# can-stm32g4.net
KiCad netlist of a schematic drawn in Altium Designer
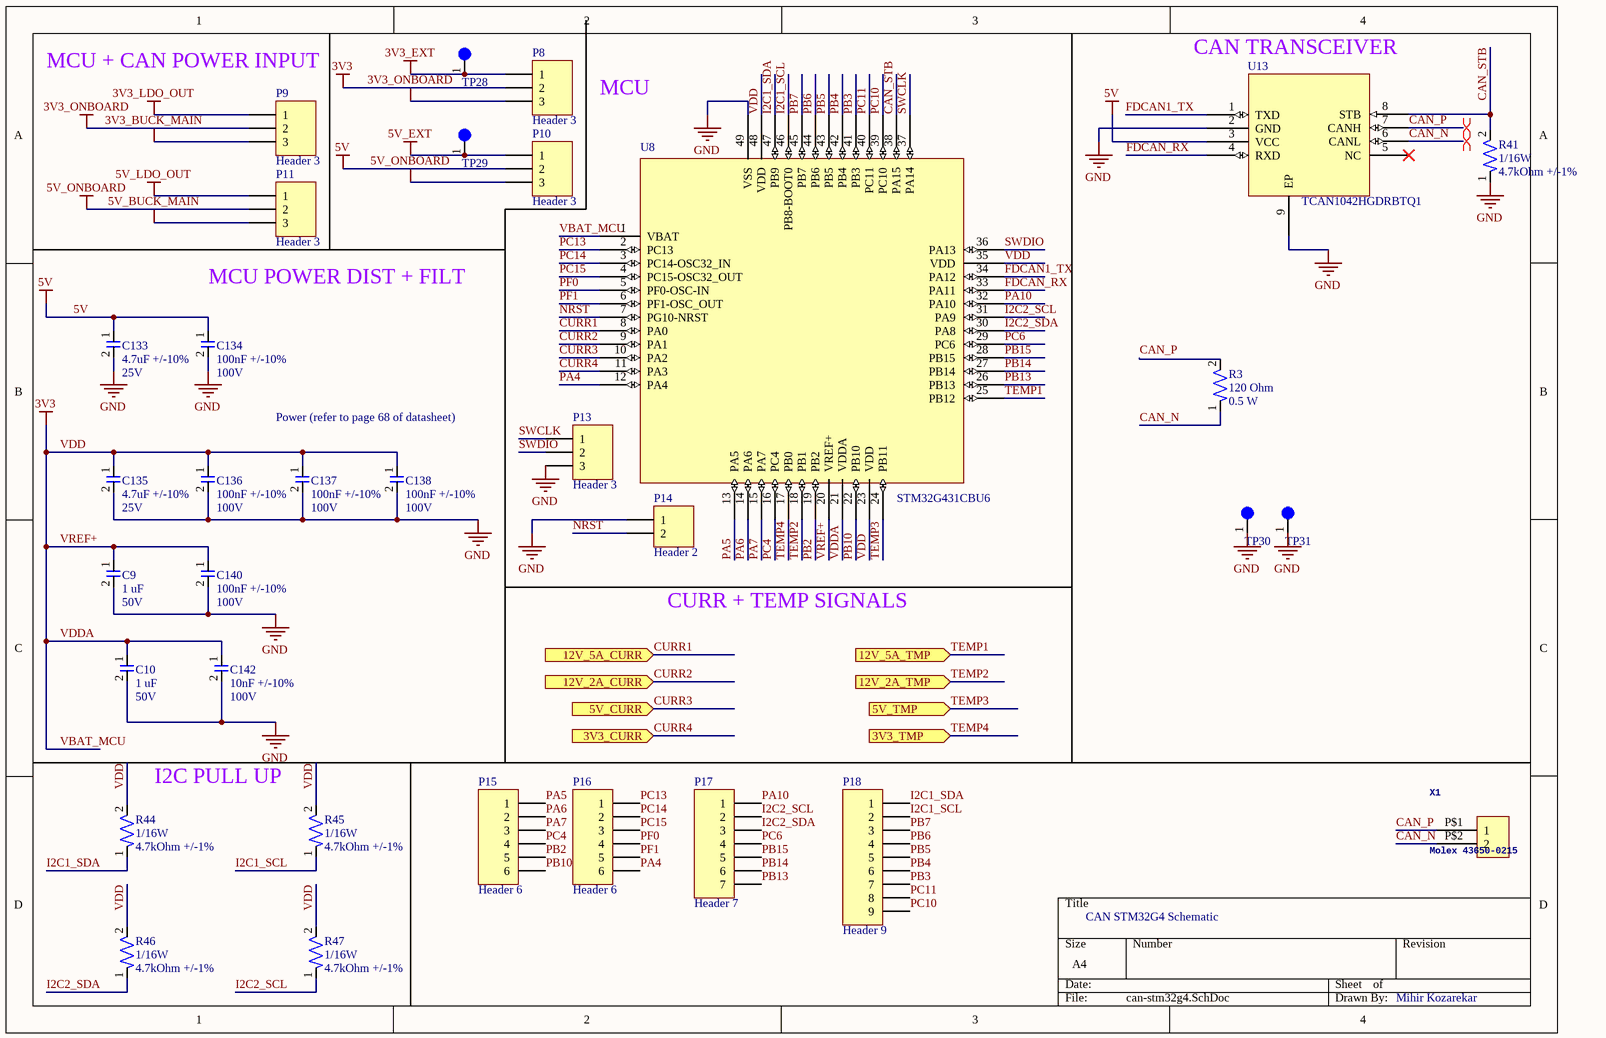
[diagram p0: can-stm32g4.SchDoc]

(export (version "E")
  (design (tool "Eeschema 10.0.6"))
  (components
    (comp (ref "C9")
      (value "UMK107AB7105KA-T")
      (footprint "CAP-0603")
      (description "1 µF ±10% 50V Ceramic Capacitor X7R 0603 (1608 Metric)")
      (fields (field (name "CAPACITANCE") "1 uF") (field (name "VOLTAGE") "50V"))
      (libsource (lib "MasterLib") (part "CAP-1U-0002"))
    )
    (comp (ref "C10")
      (value "UMK107AB7105KA-T")
      (footprint "CAP-0603")
      (description "1 µF ±10% 50V Ceramic Capacitor X7R 0603 (1608 Metric)")
      (fields (field (name "CAPACITANCE") "1 uF") (field (name "VOLTAGE") "50V"))
      (libsource (lib "MasterLib") (part "CAP-1U-0002"))
    )
    (comp (ref "C133")
      (value "TMK107BBJ475KA-T")
      (footprint "CAP-0603")
      (description "4.7 µF ±10% 25V Ceramic Capacitor X5R 0603 (1608 Metric)")
      (fields
        (field (name "MANUFACTURER") "Taiyo Yuden")
        (field (name "CAPACITANCE") "4.7uF +/-10%")
        (field (name "VOLTAGE RATING") "25V")
      )
      (libsource (lib "MasterLib") (part "CAP-4.7U-0001"))
    )
    (comp (ref "C134")
      (value "CC0603KRX7R0BB104")
      (footprint "CAP-0603")
      (description "CAP CER 0.1UF 100V X7R 0603")
      (fields
        (field (name "MANUFACTURER") "YAGEO")
        (field (name "CAPACITANCE") "100nF +/-10%")
        (field (name "VOLTAGE RATING") "100V")
      )
      (libsource (lib "MasterLib") (part "CAP-100N-0001"))
    )
    (comp (ref "C135")
      (value "TMK107BBJ475KA-T")
      (footprint "CAP-0603")
      (description "4.7 µF ±10% 25V Ceramic Capacitor X5R 0603 (1608 Metric)")
      (fields
        (field (name "MANUFACTURER") "Taiyo Yuden")
        (field (name "CAPACITANCE") "4.7uF +/-10%")
        (field (name "VOLTAGE RATING") "25V")
      )
      (libsource (lib "MasterLib") (part "CAP-4.7U-0001"))
    )
    (comp (ref "C136")
      (value "CC0603KRX7R0BB104")
      (footprint "CAP-0603")
      (description "CAP CER 0.1UF 100V X7R 0603")
      (fields
        (field (name "MANUFACTURER") "YAGEO")
        (field (name "CAPACITANCE") "100nF +/-10%")
        (field (name "VOLTAGE RATING") "100V")
      )
      (libsource (lib "MasterLib") (part "CAP-100N-0001"))
    )
    (comp (ref "C137")
      (value "CC0603KRX7R0BB104")
      (footprint "CAP-0603")
      (description "CAP CER 0.1UF 100V X7R 0603")
      (fields
        (field (name "MANUFACTURER") "YAGEO")
        (field (name "CAPACITANCE") "100nF +/-10%")
        (field (name "VOLTAGE RATING") "100V")
      )
      (libsource (lib "MasterLib") (part "CAP-100N-0001"))
    )
    (comp (ref "C138")
      (value "CC0603KRX7R0BB104")
      (footprint "CAP-0603")
      (description "CAP CER 0.1UF 100V X7R 0603")
      (fields
        (field (name "MANUFACTURER") "YAGEO")
        (field (name "CAPACITANCE") "100nF +/-10%")
        (field (name "VOLTAGE RATING") "100V")
      )
      (libsource (lib "MasterLib") (part "CAP-100N-0001"))
    )
    (comp (ref "C140")
      (value "CC0603KRX7R0BB104")
      (footprint "CAP-0603")
      (description "CAP CER 0.1UF 100V X7R 0603")
      (fields
        (field (name "MANUFACTURER") "YAGEO")
        (field (name "CAPACITANCE") "100nF +/-10%")
        (field (name "VOLTAGE RATING") "100V")
      )
      (libsource (lib "MasterLib") (part "CAP-100N-0001"))
    )
    (comp (ref "C142")
      (value "CC0402KRX7R0BB103")
      (footprint "CAP-0402")
      (description "10000 pF ±10% 100V Ceramic Capacitor X7R 0402 (1005 Metric)")
      (fields
        (field (name "MANUFACTURER") "YAGEO")
        (field (name "CAPACITANCE") "10nF +/-10%")
        (field (name "VOLTAGE RATING") "100V")
      )
      (libsource (lib "MasterLib") (part "CAP-10N-0001"))
    )
    (comp (ref "P8")
      (value "Header 3")
      (footprint "HDR1X3")
      (description "Header, 3-Pin")
      (fields (field (name "PUBLISHER") "Altium Limited"))
      (libsource (lib "Miscellaneous Connectors") (part "Header 3"))
    )
    (comp (ref "P9")
      (value "Header 3")
      (footprint "HDR1X3")
      (description "Header, 3-Pin")
      (fields (field (name "PUBLISHER") "Altium Limited"))
      (libsource (lib "Miscellaneous Connectors") (part "Header 3"))
    )
    (comp (ref "P10")
      (value "Header 3")
      (footprint "HDR1X3")
      (description "Header, 3-Pin")
      (fields (field (name "PUBLISHER") "Altium Limited"))
      (libsource (lib "Miscellaneous Connectors") (part "Header 3"))
    )
    (comp (ref "P11")
      (value "Header 3")
      (footprint "HDR1X3")
      (description "Header, 3-Pin")
      (fields (field (name "PUBLISHER") "Altium Limited"))
      (libsource (lib "Miscellaneous Connectors") (part "Header 3"))
    )
    (comp (ref "P13")
      (value "Header 3")
      (footprint "HDR1X3")
      (description "Header, 3-Pin")
      (fields (field (name "PUBLISHER") "Altium Limited"))
      (libsource (lib "Miscellaneous Connectors") (part "Header 3"))
    )
    (comp (ref "P14")
      (value "Header 2")
      (footprint "HDR1X2")
      (description "Header, 2-Pin")
      (fields (field (name "PUBLISHER") "Altium Limited"))
      (libsource (lib "Miscellaneous Connectors") (part "Header 2"))
    )
    (comp (ref "P15")
      (value "Header 6")
      (footprint "HDR1X6")
      (description "Header, 6-Pin")
      (fields (field (name "PUBLISHER") "Altium Limited"))
      (libsource (lib "Miscellaneous Connectors") (part "Header 6"))
    )
    (comp (ref "P16")
      (value "Header 6")
      (footprint "HDR1X6")
      (description "Header, 6-Pin")
      (fields (field (name "PUBLISHER") "Altium Limited"))
      (libsource (lib "Miscellaneous Connectors") (part "Header 6"))
    )
    (comp (ref "P17")
      (value "Header 7")
      (footprint "HDR1X7")
      (description "Header, 7-Pin")
      (fields (field (name "PUBLISHER") "Altium Limited"))
      (libsource (lib "Miscellaneous Connectors") (part "Header 7"))
    )
    (comp (ref "P18")
      (value "Header 9")
      (footprint "HDR1X9")
      (description "Header, 9-Pin")
      (fields (field (name "PUBLISHER") "Altium Limited"))
      (libsource (lib "Miscellaneous Connectors") (part "Header 9"))
    )
    (comp (ref "R3")
      (value "CRGH1206F120R")
      (footprint "RES-1206")
      (description "120 Ohms ±1% 0.5W, 1/2W Chip Resistor 1206 (3216 Metric) Thick Film")
      (fields
        (field (name "TOLERANCE") "1%")
        (field (name "RESISTANCE") "120 Ohm")
        (field (name "POWER") "0.5 W")
      )
      (libsource (lib "MasterLib") (part "RES-120-0002"))
    )
    (comp (ref "R41")
      (value "RC0402FR-074K7P")
      (footprint "RES-0402")
      (description "RES SMD 4.7K OHM 1% 1/16W 0402")
      (fields
        (field (name "MANUFACTURER") "YAGEO")
        (field (name "POWER RATING") "1/16W")
        (field (name "RESISTANCE") "4.7kOhm +/-1%")
      )
      (libsource (lib "MasterLib") (part "RES-4.7K-0001"))
    )
    (comp (ref "R44")
      (value "RC0402FR-074K7P")
      (footprint "RES-0402")
      (description "RES SMD 4.7K OHM 1% 1/16W 0402")
      (fields
        (field (name "MANUFACTURER") "YAGEO")
        (field (name "POWER RATING") "1/16W")
        (field (name "RESISTANCE") "4.7kOhm +/-1%")
      )
      (libsource (lib "MasterLib") (part "RES-4.7K-0001"))
    )
    (comp (ref "R45")
      (value "RC0402FR-074K7P")
      (footprint "RES-0402")
      (description "RES SMD 4.7K OHM 1% 1/16W 0402")
      (fields
        (field (name "MANUFACTURER") "YAGEO")
        (field (name "POWER RATING") "1/16W")
        (field (name "RESISTANCE") "4.7kOhm +/-1%")
      )
      (libsource (lib "MasterLib") (part "RES-4.7K-0001"))
    )
    (comp (ref "R46")
      (value "RC0402FR-074K7P")
      (footprint "RES-0402")
      (description "RES SMD 4.7K OHM 1% 1/16W 0402")
      (fields
        (field (name "MANUFACTURER") "YAGEO")
        (field (name "POWER RATING") "1/16W")
        (field (name "RESISTANCE") "4.7kOhm +/-1%")
      )
      (libsource (lib "MasterLib") (part "RES-4.7K-0001"))
    )
    (comp (ref "R47")
      (value "RC0402FR-074K7P")
      (footprint "RES-0402")
      (description "RES SMD 4.7K OHM 1% 1/16W 0402")
      (fields
        (field (name "MANUFACTURER") "YAGEO")
        (field (name "POWER RATING") "1/16W")
        (field (name "RESISTANCE") "4.7kOhm +/-1%")
      )
      (libsource (lib "MasterLib") (part "RES-4.7K-0001"))
    )
    (comp (ref "TP28")
      (value "5003")
      (footprint "TEST-POINT-0001")
      (description "Oranange PC Test Point, Miniature Phoisphor Bronze Silver Plating Through Hole Mounting Type")
      (libsource (lib "MasterLib") (part "TEST-POINT-0001"))
    )
    (comp (ref "TP29")
      (value "5003")
      (footprint "TEST-POINT-0001")
      (description "Oranange PC Test Point, Miniature Phoisphor Bronze Silver Plating Through Hole Mounting Type")
      (libsource (lib "MasterLib") (part "TEST-POINT-0001"))
    )
    (comp (ref "TP30")
      (value "5003")
      (footprint "TEST-POINT-0001")
      (description "Oranange PC Test Point, Miniature Phoisphor Bronze Silver Plating Through Hole Mounting Type")
      (libsource (lib "MasterLib") (part "TEST-POINT-0001"))
    )
    (comp (ref "TP31")
      (value "5003")
      (footprint "TEST-POINT-0001")
      (description "Oranange PC Test Point, Miniature Phoisphor Bronze Silver Plating Through Hole Mounting Type")
      (libsource (lib "MasterLib") (part "TEST-POINT-0001"))
    )
    (comp (ref "U8")
      (value "STM32G431CBU6")
      (footprint "MCU-UFQFPN48")
      (libsource (lib "MasterLib") (part "IC-STM32G431CBU6"))
    )
    (comp (ref "U13")
      (value "TCAN1042HGDRBTQ1")
      (footprint "IC-8-VSON")
      (description "1/1 Transceiver CANbus 8-VSON (3x3)")
      (fields (field (name "MANUFACTURER") "Texas Instrument"))
      (libsource (lib "MasterLib") (part "IC-CAN-TRANSCEIVER-0002"))
    )
    (comp (ref "X1")
      (value "Molex 43650-0215")
      (footprint "43650-0215")
      (libsource (lib "Molex Microfit") (part "Micro-Fit Molex 2 Pin Vertical"))
    )
  )
  (nets
    (net (code "1") (name "/CAN_N") (class "Default")
      (node (ref "R3") (pin "1") (pinfunction "1_1") (pintype "passive"))
      (node (ref "U13") (pin "6") (pinfunction "CANL_6") (pintype "bidirectional"))
      (node (ref "X1") (pin "P$2") (pinfunction "2_P$2") (pintype "passive"))
    )
    (net (code "2") (name "/CAN_P") (class "Default")
      (node (ref "R3") (pin "2") (pinfunction "2_2") (pintype "passive"))
      (node (ref "U13") (pin "7") (pinfunction "CANH_7") (pintype "bidirectional"))
      (node (ref "X1") (pin "P$1") (pinfunction "1_P$1") (pintype "passive"))
    )
    (net (code "3") (name "/CAN_STB") (class "Default")
      (node (ref "R41") (pin "2") (pinfunction "2_2") (pintype "passive"))
      (node (ref "U13") (pin "8") (pinfunction "STB_8") (pintype "input"))
      (node (ref "U8") (pin "38") (pinfunction "PA15_38") (pintype "bidirectional"))
    )
    (net (code "4") (name "/CURR1") (class "Default")
      (node (ref "U8") (pin "8") (pinfunction "PA0_8") (pintype "bidirectional"))
    )
    (net (code "5") (name "/CURR2") (class "Default")
      (node (ref "U8") (pin "9") (pinfunction "PA1_9") (pintype "bidirectional"))
    )
    (net (code "6") (name "/CURR3") (class "Default")
      (node (ref "U8") (pin "10") (pinfunction "PA2_10") (pintype "bidirectional"))
    )
    (net (code "7") (name "/CURR4") (class "Default")
      (node (ref "U8") (pin "11") (pinfunction "PA3_11") (pintype "bidirectional"))
    )
    (net (code "8") (name "/FDCAN1_TX") (class "Default")
      (node (ref "U13") (pin "1") (pinfunction "TXD_1") (pintype "bidirectional"))
      (node (ref "U8") (pin "34") (pinfunction "PA12_34") (pintype "bidirectional"))
    )
    (net (code "9") (name "/FDCAN_RX") (class "Default")
      (node (ref "U13") (pin "4") (pinfunction "RXD_4") (pintype "bidirectional"))
      (node (ref "U8") (pin "33") (pinfunction "PA11_33") (pintype "bidirectional"))
    )
    (net (code "10") (name "/I2C1_SCL") (class "Default")
      (node (ref "P18") (pin "2") (pinfunction "2_2") (pintype "passive"))
      (node (ref "R45") (pin "1") (pinfunction "1_1") (pintype "passive"))
      (node (ref "U8") (pin "46") (pinfunction "PB8-BOOT0_46") (pintype "bidirectional"))
    )
    (net (code "11") (name "/I2C1_SDA") (class "Default")
      (node (ref "P18") (pin "1") (pinfunction "1_1") (pintype "passive"))
      (node (ref "R44") (pin "1") (pinfunction "1_1") (pintype "passive"))
      (node (ref "U8") (pin "47") (pinfunction "PB9_47") (pintype "bidirectional"))
    )
    (net (code "12") (name "/I2C2_SCL") (class "Default")
      (node (ref "P17") (pin "2") (pinfunction "2_2") (pintype "passive"))
      (node (ref "R47") (pin "1") (pinfunction "1_1") (pintype "passive"))
      (node (ref "U8") (pin "31") (pinfunction "PA9_31") (pintype "bidirectional"))
    )
    (net (code "13") (name "/I2C2_SDA") (class "Default")
      (node (ref "P17") (pin "3") (pinfunction "3_3") (pintype "passive"))
      (node (ref "R46") (pin "1") (pinfunction "1_1") (pintype "passive"))
      (node (ref "U8") (pin "30") (pinfunction "PA8_30") (pintype "bidirectional"))
    )
    (net (code "14") (name "/NRST") (class "Default")
      (node (ref "P14") (pin "2") (pinfunction "2_2") (pintype "passive"))
      (node (ref "U8") (pin "7") (pinfunction "PG10-NRST_7") (pintype "bidirectional"))
    )
    (net (code "15") (name "/PA4") (class "Default")
      (node (ref "P16") (pin "6") (pinfunction "6_6") (pintype "passive"))
      (node (ref "U8") (pin "12") (pinfunction "PA4_12") (pintype "bidirectional"))
    )
    (net (code "16") (name "/PA5") (class "Default")
      (node (ref "P15") (pin "1") (pinfunction "1_1") (pintype "passive"))
      (node (ref "U8") (pin "13") (pinfunction "PA5_13") (pintype "bidirectional"))
    )
    (net (code "17") (name "/PA6") (class "Default")
      (node (ref "P15") (pin "2") (pinfunction "2_2") (pintype "passive"))
      (node (ref "U8") (pin "14") (pinfunction "PA6_14") (pintype "bidirectional"))
    )
    (net (code "18") (name "/PA7") (class "Default")
      (node (ref "P15") (pin "3") (pinfunction "3_3") (pintype "passive"))
      (node (ref "U8") (pin "15") (pinfunction "PA7_15") (pintype "bidirectional"))
    )
    (net (code "19") (name "/PA10") (class "Default")
      (node (ref "P17") (pin "1") (pinfunction "1_1") (pintype "passive"))
      (node (ref "U8") (pin "32") (pinfunction "PA10_32") (pintype "bidirectional"))
    )
    (net (code "20") (name "/PB2") (class "Default")
      (node (ref "P15") (pin "5") (pinfunction "5_5") (pintype "passive"))
      (node (ref "U8") (pin "19") (pinfunction "PB2_19") (pintype "bidirectional"))
    )
    (net (code "21") (name "/PB3") (class "Default")
      (node (ref "P18") (pin "7") (pinfunction "7_7") (pintype "passive"))
      (node (ref "U8") (pin "41") (pinfunction "PB3_41") (pintype "bidirectional"))
    )
    (net (code "22") (name "/PB4") (class "Default")
      (node (ref "P18") (pin "6") (pinfunction "6_6") (pintype "passive"))
      (node (ref "U8") (pin "42") (pinfunction "PB4_42") (pintype "bidirectional"))
    )
    (net (code "23") (name "/PB5") (class "Default")
      (node (ref "P18") (pin "5") (pinfunction "5_5") (pintype "passive"))
      (node (ref "U8") (pin "43") (pinfunction "PB5_43") (pintype "bidirectional"))
    )
    (net (code "24") (name "/PB6") (class "Default")
      (node (ref "P18") (pin "4") (pinfunction "4_4") (pintype "passive"))
      (node (ref "U8") (pin "44") (pinfunction "PB6_44") (pintype "bidirectional"))
    )
    (net (code "25") (name "/PB7") (class "Default")
      (node (ref "P18") (pin "3") (pinfunction "3_3") (pintype "passive"))
      (node (ref "U8") (pin "45") (pinfunction "PB7_45") (pintype "bidirectional"))
    )
    (net (code "26") (name "/PB10") (class "Default")
      (node (ref "P15") (pin "6") (pinfunction "6_6") (pintype "passive"))
      (node (ref "U8") (pin "22") (pinfunction "PB10_22") (pintype "bidirectional"))
    )
    (net (code "27") (name "/PB13") (class "Default")
      (node (ref "P17") (pin "7") (pinfunction "7_7") (pintype "passive"))
      (node (ref "U8") (pin "26") (pinfunction "PB13_26") (pintype "bidirectional"))
    )
    (net (code "28") (name "/PB14") (class "Default")
      (node (ref "P17") (pin "6") (pinfunction "6_6") (pintype "passive"))
      (node (ref "U8") (pin "27") (pinfunction "PB14_27") (pintype "bidirectional"))
    )
    (net (code "29") (name "/PB15") (class "Default")
      (node (ref "P17") (pin "5") (pinfunction "5_5") (pintype "passive"))
      (node (ref "U8") (pin "28") (pinfunction "PB15_28") (pintype "bidirectional"))
    )
    (net (code "30") (name "/PC4") (class "Default")
      (node (ref "P15") (pin "4") (pinfunction "4_4") (pintype "passive"))
      (node (ref "U8") (pin "16") (pinfunction "PC4_16") (pintype "bidirectional"))
    )
    (net (code "31") (name "/PC6") (class "Default")
      (node (ref "P17") (pin "4") (pinfunction "4_4") (pintype "passive"))
      (node (ref "U8") (pin "29") (pinfunction "PC6_29") (pintype "bidirectional"))
    )
    (net (code "32") (name "/PC10") (class "Default")
      (node (ref "P18") (pin "9") (pinfunction "9_9") (pintype "passive"))
      (node (ref "U8") (pin "39") (pinfunction "PC10_39") (pintype "bidirectional"))
    )
    (net (code "33") (name "/PC11") (class "Default")
      (node (ref "P18") (pin "8") (pinfunction "8_8") (pintype "passive"))
      (node (ref "U8") (pin "40") (pinfunction "PC11_40") (pintype "bidirectional"))
    )
    (net (code "34") (name "/PC13") (class "Default")
      (node (ref "P16") (pin "1") (pinfunction "1_1") (pintype "passive"))
      (node (ref "U8") (pin "2") (pinfunction "PC13_2") (pintype "bidirectional"))
    )
    (net (code "35") (name "/PC14") (class "Default")
      (node (ref "P16") (pin "2") (pinfunction "2_2") (pintype "passive"))
      (node (ref "U8") (pin "3") (pinfunction "PC14-OSC32_IN_3") (pintype "bidirectional"))
    )
    (net (code "36") (name "/PC15") (class "Default")
      (node (ref "P16") (pin "3") (pinfunction "3_3") (pintype "passive"))
      (node (ref "U8") (pin "4") (pinfunction "PC15-OSC32_OUT_4") (pintype "bidirectional"))
    )
    (net (code "37") (name "/PF0") (class "Default")
      (node (ref "P16") (pin "4") (pinfunction "4_4") (pintype "passive"))
      (node (ref "U8") (pin "5") (pinfunction "PF0-OSC-IN_5") (pintype "bidirectional"))
    )
    (net (code "38") (name "/PF1") (class "Default")
      (node (ref "P16") (pin "5") (pinfunction "5_5") (pintype "passive"))
      (node (ref "U8") (pin "6") (pinfunction "PF1-OSC_OUT_6") (pintype "bidirectional"))
    )
    (net (code "39") (name "/SWCLK") (class "Default")
      (node (ref "P13") (pin "1") (pinfunction "1_1") (pintype "passive"))
      (node (ref "U8") (pin "37") (pinfunction "PA14_37") (pintype "bidirectional"))
    )
    (net (code "40") (name "/SWDIO") (class "Default")
      (node (ref "P13") (pin "2") (pinfunction "2_2") (pintype "passive"))
      (node (ref "U8") (pin "36") (pinfunction "PA13_36") (pintype "bidirectional"))
    )
    (net (code "41") (name "/TEMP1") (class "Default")
      (node (ref "U8") (pin "25") (pinfunction "PB12_25") (pintype "bidirectional"))
    )
    (net (code "42") (name "/TEMP2") (class "Default")
      (node (ref "U8") (pin "18") (pinfunction "PB1_18") (pintype "bidirectional"))
    )
    (net (code "43") (name "/TEMP3") (class "Default")
      (node (ref "U8") (pin "24") (pinfunction "PB11_24") (pintype "bidirectional"))
    )
    (net (code "44") (name "/TEMP4") (class "Default")
      (node (ref "U8") (pin "17") (pinfunction "PB0_17") (pintype "bidirectional"))
    )
    (net (code "45") (name "3V3") (class "Default")
      (node (ref "C10") (pin "1") (pinfunction "1_1") (pintype "passive"))
      (node (ref "C135") (pin "1") (pinfunction "1_1") (pintype "passive"))
      (node (ref "C136") (pin "1") (pinfunction "1_1") (pintype "passive"))
      (node (ref "C137") (pin "1") (pinfunction "1_1") (pintype "passive"))
      (node (ref "C138") (pin "1") (pinfunction "1_1") (pintype "passive"))
      (node (ref "C140") (pin "1") (pinfunction "1_1") (pintype "passive"))
      (node (ref "C142") (pin "1") (pinfunction "1_1") (pintype "passive"))
      (node (ref "C9") (pin "1") (pinfunction "1_1") (pintype "passive"))
      (node (ref "P8") (pin "2") (pinfunction "2_2") (pintype "passive"))
      (node (ref "R44") (pin "2") (pinfunction "2_2") (pintype "passive"))
      (node (ref "R45") (pin "2") (pinfunction "2_2") (pintype "passive"))
      (node (ref "R46") (pin "2") (pinfunction "2_2") (pintype "passive"))
      (node (ref "R47") (pin "2") (pinfunction "2_2") (pintype "passive"))
      (node (ref "U8") (pin "1") (pinfunction "VBAT_1") (pintype "power_in"))
      (node (ref "U8") (pin "20") (pinfunction "VREF+_20") (pintype "power_in"))
      (node (ref "U8") (pin "21") (pinfunction "VDDA_21") (pintype "power_in"))
      (node (ref "U8") (pin "23") (pinfunction "VDD_23") (pintype "power_in"))
      (node (ref "U8") (pin "35") (pinfunction "VDD_35") (pintype "power_in"))
      (node (ref "U8") (pin "48") (pinfunction "VDD_48") (pintype "power_in"))
    )
    (net (code "46") (name "3V3_BUCK_MAIN") (class "Default")
      (node (ref "P9") (pin "3") (pinfunction "3_3") (pintype "passive"))
    )
    (net (code "47") (name "3V3_EXT") (class "Default")
      (node (ref "P8") (pin "1") (pinfunction "1_1") (pintype "passive"))
      (node (ref "TP28") (pin "1") (pinfunction "0_1") (pintype "passive"))
    )
    (net (code "48") (name "3V3_LDO_OUT") (class "Default")
      (node (ref "P9") (pin "1") (pinfunction "1_1") (pintype "passive"))
    )
    (net (code "49") (name "3V3_ONBOARD") (class "Default")
      (node (ref "P8") (pin "3") (pinfunction "3_3") (pintype "passive"))
      (node (ref "P9") (pin "2") (pinfunction "2_2") (pintype "passive"))
    )
    (net (code "50") (name "5V") (class "Default")
      (node (ref "C133") (pin "1") (pinfunction "1_1") (pintype "passive"))
      (node (ref "C134") (pin "1") (pinfunction "1_1") (pintype "passive"))
      (node (ref "P10") (pin "2") (pinfunction "2_2") (pintype "passive"))
      (node (ref "U13") (pin "3") (pinfunction "VCC_3") (pintype "power_in"))
    )
    (net (code "51") (name "5V_BUCK_MAIN") (class "Default")
      (node (ref "P11") (pin "3") (pinfunction "3_3") (pintype "passive"))
    )
    (net (code "52") (name "5V_EXT") (class "Default")
      (node (ref "P10") (pin "1") (pinfunction "1_1") (pintype "passive"))
      (node (ref "TP29") (pin "1") (pinfunction "0_1") (pintype "passive"))
    )
    (net (code "53") (name "5V_LDO_OUT") (class "Default")
      (node (ref "P11") (pin "1") (pinfunction "1_1") (pintype "passive"))
    )
    (net (code "54") (name "5V_ONBOARD") (class "Default")
      (node (ref "P10") (pin "3") (pinfunction "3_3") (pintype "passive"))
      (node (ref "P11") (pin "2") (pinfunction "2_2") (pintype "passive"))
    )
    (net (code "55") (name "GND") (class "Default")
      (node (ref "C10") (pin "2") (pinfunction "2_2") (pintype "passive"))
      (node (ref "C133") (pin "2") (pinfunction "2_2") (pintype "passive"))
      (node (ref "C134") (pin "2") (pinfunction "2_2") (pintype "passive"))
      (node (ref "C135") (pin "2") (pinfunction "2_2") (pintype "passive"))
      (node (ref "C136") (pin "2") (pinfunction "2_2") (pintype "passive"))
      (node (ref "C137") (pin "2") (pinfunction "2_2") (pintype "passive"))
      (node (ref "C138") (pin "2") (pinfunction "2_2") (pintype "passive"))
      (node (ref "C140") (pin "2") (pinfunction "2_2") (pintype "passive"))
      (node (ref "C142") (pin "2") (pinfunction "2_2") (pintype "passive"))
      (node (ref "C9") (pin "2") (pinfunction "2_2") (pintype "passive"))
      (node (ref "P13") (pin "3") (pinfunction "3_3") (pintype "passive"))
      (node (ref "P14") (pin "1") (pinfunction "1_1") (pintype "passive"))
      (node (ref "R41") (pin "1") (pinfunction "1_1") (pintype "passive"))
      (node (ref "TP30") (pin "1") (pinfunction "0_1") (pintype "passive"))
      (node (ref "TP31") (pin "1") (pinfunction "0_1") (pintype "passive"))
      (node (ref "U13") (pin "2") (pinfunction "GND_2") (pintype "power_in"))
      (node (ref "U13") (pin "9") (pinfunction "EP_9") (pintype "power_in"))
      (node (ref "U8") (pin "49") (pinfunction "VSS_49") (pintype "power_in"))
    )
    (net (code "56") (name "unconnected-(U13-NC-Pad5)") (class "Default")
      (node (ref "U13") (pin "5") (pinfunction "NC_5") (pintype "power_in+no_connect"))
    )
  )
)
